# SD_Card.net
KiCad netlist of a schematic drawn in Altium Designer
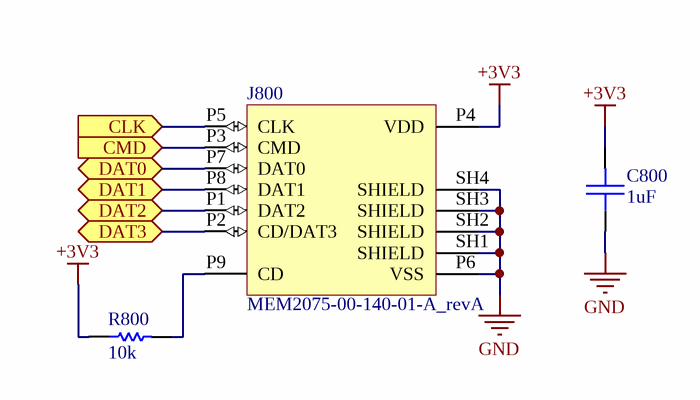
[diagram p0: SD_Card.SchDoc]

(export (version "E")
  (design (tool "Eeschema 10.0.6"))
  (components
    (comp (ref "C800")
      (value "1uF")
      (footprint "0603_CAP")
      (libsource (lib "Moonlight_Components") (part "Capacitor"))
    )
    (comp (ref "J800")
      (value "MEM2075-00-140-01-A_revA")
      (footprint "MEM2075-00-140-01-A_revA")
      (description "Push-Push style MicroSD Card holder\r\nDigikey part no. 2073-MEM2075-00-140-01-ACT-ND")
      (fields (field (name "MANUFACTURER") "GCT"))
      (libsource (lib "Moonlight_Components") (part "MicroSD Card holder"))
    )
    (comp (ref "R800")
      (value "10k")
      (footprint "0603_RES")
      (libsource (lib "Moonlight_Components") (part "Resistor"))
    )
  )
  (nets
    (net (code "1") (name "+3V3") (class "Default")
      (node (ref "C800") (pin "1") (pinfunction "1_1") (pintype "passive"))
      (node (ref "J800") (pin "P4") (pinfunction "VDD_P4") (pintype "power_in"))
      (node (ref "R800") (pin "1") (pinfunction "1_1") (pintype "passive"))
    )
    (net (code "2") (name "/CLK") (class "Default")
      (node (ref "J800") (pin "P5") (pinfunction "CLK_P5") (pintype "bidirectional"))
    )
    (net (code "3") (name "/CMD") (class "Default")
      (node (ref "J800") (pin "P3") (pinfunction "CMD_P3") (pintype "bidirectional"))
    )
    (net (code "4") (name "/DAT0") (class "Default")
      (node (ref "J800") (pin "P7") (pinfunction "DAT0_P7") (pintype "bidirectional"))
    )
    (net (code "5") (name "/DAT1") (class "Default")
      (node (ref "J800") (pin "P8") (pinfunction "DAT1_P8") (pintype "bidirectional"))
    )
    (net (code "6") (name "/DAT2") (class "Default")
      (node (ref "J800") (pin "P1") (pinfunction "DAT2_P1") (pintype "bidirectional"))
    )
    (net (code "7") (name "/DAT3") (class "Default")
      (node (ref "J800") (pin "P2") (pinfunction "CD/DAT3_P2") (pintype "bidirectional"))
    )
    (net (code "8") (name "GND") (class "Default")
      (node (ref "C800") (pin "2") (pinfunction "2_2") (pintype "passive"))
      (node (ref "J800") (pin "P6") (pinfunction "VSS_P6") (pintype "power_in"))
      (node (ref "J800") (pin "SH1") (pinfunction "SHIELD_SH1") (pintype "power_in"))
      (node (ref "J800") (pin "SH2") (pinfunction "SHIELD_SH2") (pintype "passive"))
      (node (ref "J800") (pin "SH3") (pinfunction "SHIELD_SH3") (pintype "passive"))
      (node (ref "J800") (pin "SH4") (pinfunction "SHIELD_SH4") (pintype "passive"))
    )
    (net (code "9") (name "Net-(J800-CD)") (class "Default")
      (node (ref "J800") (pin "P9") (pinfunction "CD_P9") (pintype "passive"))
      (node (ref "R800") (pin "2") (pinfunction "2_2") (pintype "passive"))
    )
  )
)
